# 23cm_amplifier.net
KiCad netlist of a schematic drawn in Altium Designer
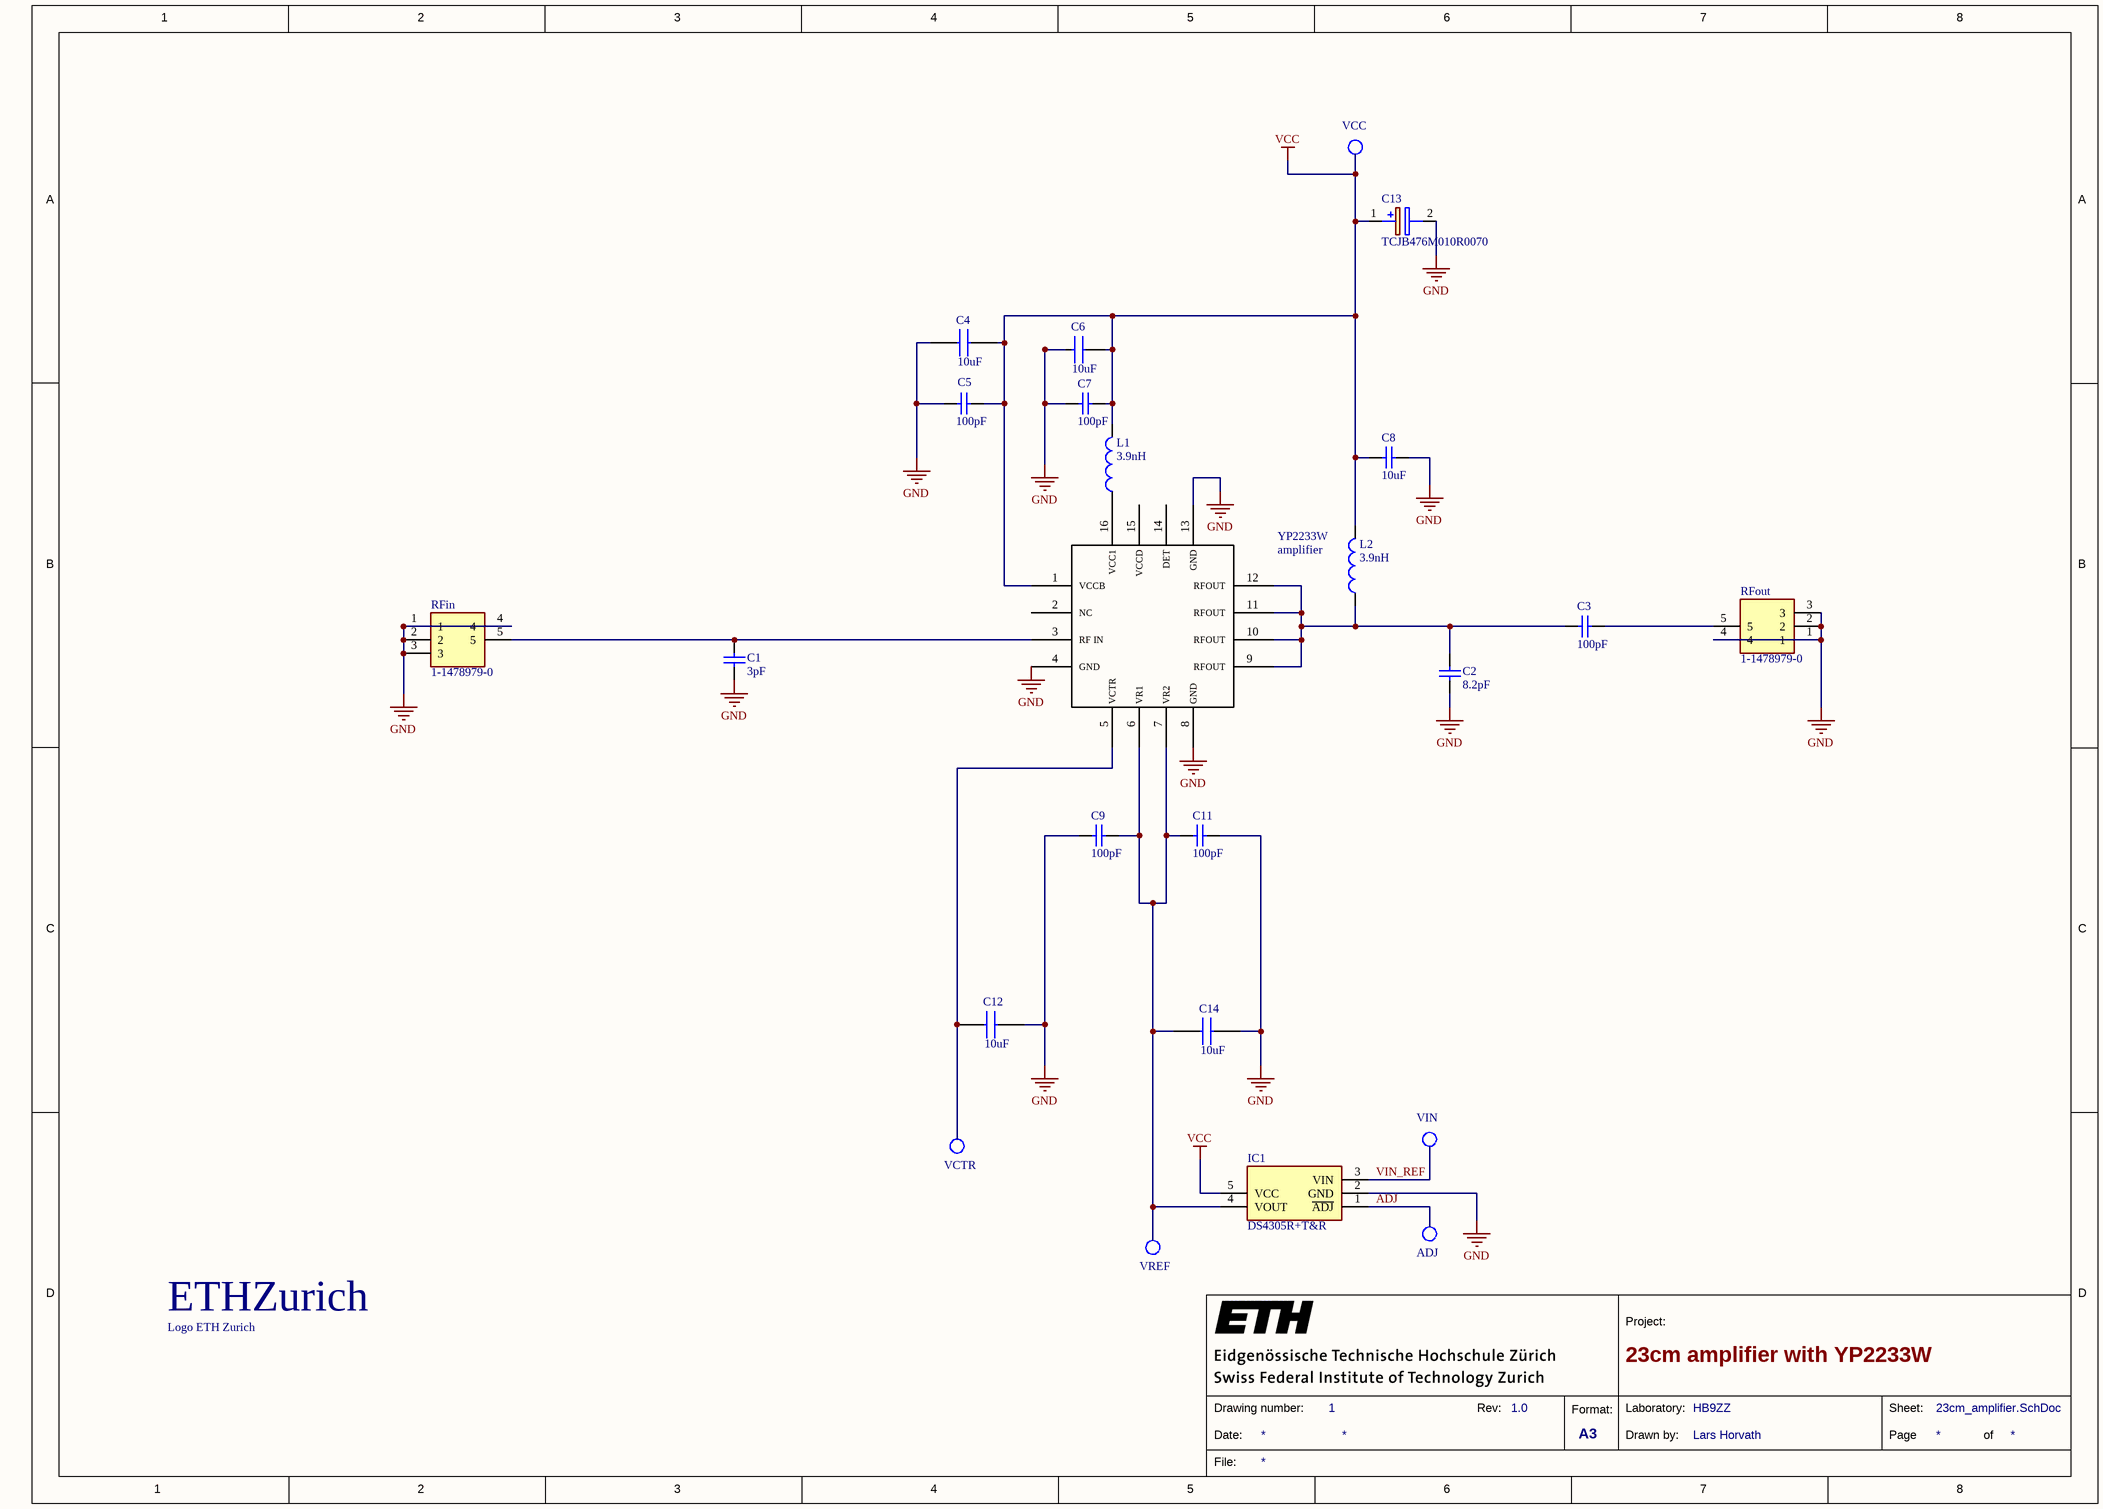
[diagram p0: 23cm_amplifier.SchDoc]

(export (version "E")
  (design (tool "Eeschema 10.0.6"))
  (components
    (comp (ref "A1")
      (value "Logo ETH Zurich")
      (footprint "eth-zurich_3mm")
      (libsource (lib "ETHZ Vault") (part "Logo ETH Zurich"))
    )
    (comp (ref "C1")
      (value "3pF")
      (footprint "CAPC0402(1005)70_N")
      (description "Silizium-HF-Kondensatoren / Dünnfilm 25V 3pF .05pFTol ThinFilm 0402")
      (fields (field (name "TOLERANCE") "5%") (field (name "MANUFACTURER") "Murata"))
      (libsource (lib "ETHZ Vault") (part "CAP"))
    )
    (comp (ref "C2")
      (value "8.2pF")
      (footprint "CAPC0402(1005)70_N")
      (description "Silizium-HF-Kondensatoren / Dünnfilm 16V 8.2pF .1pFTol ThinFilm 0402\r\nRoHS-konform")
      (fields (field (name "TOLERANCE") "5%") (field (name "MANUFACTURER") "Murata"))
      (libsource (lib "ETHZ Vault") (part "CAP"))
    )
    (comp (ref "C3")
      (value "100pF")
      (footprint "CAPC0402(1005)70_N")
      (fields
        (field (name "TOLERANCE") "5%")
        (field (name "MANUFACTURER") "TDK")
        (field (name "MANUFACTURER PART NUMBER") "C1005C0G1H101J050BE")
      )
      (libsource (lib "ETHZ Vault") (part "CAP"))
    )
    (comp (ref "C4")
      (value "C2012X8L1A106K125AC")
      (footprint "SamacSys:CAPC2012X145N")
      (description "Kondensator aus mehreren Keramikschichten MLCC - SMD/SMT 0805 10VDC 10uF 10% X8L")
      (fields (field (name "MOUSER PART NUMBER") "810-C2012X8L106K125C") (field (name "CAPACITY") "10uF"))
      (libsource (lib "*") (part "C2012X8L1A106K125AC"))
    )
    (comp (ref "C5")
      (value "100pF")
      (footprint "CAPC0402(1005)70_N")
      (fields
        (field (name "TOLERANCE") "5%")
        (field (name "MANUFACTURER") "TDK")
        (field (name "MANUFACTURER PART NUMBER") "C1005C0G1H101J050BE")
      )
      (libsource (lib "ETHZ Vault") (part "CAP"))
    )
    (comp (ref "C6")
      (value "C2012X8L1A106K125AC")
      (footprint "SamacSys:CAPC2012X145N")
      (description "Kondensator aus mehreren Keramikschichten MLCC - SMD/SMT 0805 10VDC 10uF 10% X8L")
      (fields (field (name "MOUSER PART NUMBER") "810-C2012X8L106K125C") (field (name "CAPACITY") "10uF"))
      (libsource (lib "*") (part "C2012X8L1A106K125AC"))
    )
    (comp (ref "C7")
      (value "100pF")
      (footprint "CAPC0402(1005)70_N")
      (fields
        (field (name "TOLERANCE") "5%")
        (field (name "MANUFACTURER") "TDK")
        (field (name "MANUFACTURER PART NUMBER") "C1005C0G1H101J050BE")
      )
      (libsource (lib "ETHZ Vault") (part "CAP"))
    )
    (comp (ref "C8")
      (value "10uF")
      (footprint "CAPC0402(1005)70_N")
      (description "Kondensator aus mehreren Keramikschichten MLCC - SMD/SMT 10UF 6.3V 20% 0402\r\nRoHS-konform")
      (fields (field (name "TOLERANCE") "5%") (field (name "MANUFACTURER") "Murata"))
      (libsource (lib "ETHZ Vault") (part "CAP"))
    )
    (comp (ref "C9")
      (value "100pF")
      (footprint "CAPC0402(1005)70_N")
      (fields
        (field (name "TOLERANCE") "5%")
        (field (name "MANUFACTURER") "TDK")
        (field (name "MANUFACTURER PART NUMBER") "C1005C0G1H101J050BE")
      )
      (libsource (lib "ETHZ Vault") (part "CAP"))
    )
    (comp (ref "C11")
      (value "100pF")
      (footprint "CAPC0402(1005)70_N")
      (fields
        (field (name "TOLERANCE") "5%")
        (field (name "MANUFACTURER") "TDK")
        (field (name "MANUFACTURER PART NUMBER") "C1005C0G1H101J050BE")
      )
      (libsource (lib "ETHZ Vault") (part "CAP"))
    )
    (comp (ref "C12")
      (value "C2012X8L1A106K125AC")
      (footprint "SamacSys:CAPC2012X145N")
      (description "Kondensator aus mehreren Keramikschichten MLCC - SMD/SMT 0805 10VDC 10uF 10% X8L")
      (fields (field (name "MOUSER PART NUMBER") "810-C2012X8L106K125C") (field (name "CAPACITY") "10uF"))
      (libsource (lib "*") (part "C2012X8L1A106K125AC"))
    )
    (comp (ref "C13")
      (value "TCJB476M010R0070")
      (footprint "SamacSys:CAPPM3528X210N")
      (description "Tantalum Capacitors - Polymer 10V 47uF 20% 1210 ESR=70mOhm")
      (fields (field (name "MOUSER PART NUMBER") "581-TCJB476M10R70"))
      (libsource (lib "*") (part "TCJB476M010R0070"))
    )
    (comp (ref "C14")
      (value "C2012X8L1A106K125AC")
      (footprint "SamacSys:CAPC2012X145N")
      (description "Kondensator aus mehreren Keramikschichten MLCC - SMD/SMT 0805 10VDC 10uF 10% X8L")
      (fields (field (name "MOUSER PART NUMBER") "810-C2012X8L106K125C") (field (name "CAPACITY") "10uF"))
      (libsource (lib "*") (part "C2012X8L1A106K125AC"))
    )
    (comp (ref "IC1")
      (value "DS4305R+T&R")
      (footprint "SamacSys:SOT95P280X145-5N")
      (description "Programmable Reference Voltage for 2.65V")
      (fields (field (name "MOUSER PART NUMBER") "700-DS4305RT&R"))
      (libsource (lib "*") (part "DS4305R+T&R"))
    )
    (comp (ref "L1")
      (value "3.9nH")
      (footprint "INDC1005X07N")
      (description "Festinduktivitäten 0402 3.9nH 1950mA 0.03ohms 10GHz")
      (fields (field (name "TOLERANCE") "5%") (field (name "Comment") "LQW15AN3N9B8ZD"))
      (libsource (lib "ETHZ Vault") (part "IND"))
    )
    (comp (ref "L2")
      (value "3.9nH")
      (footprint "INDC1005X07N")
      (description "Festinduktivitäten 0402 3.9nH 1950mA 0.03ohms 10GHz")
      (fields (field (name "TOLERANCE") "5%") (field (name "Comment") "LQW15AN3N9B8ZD"))
      (libsource (lib "ETHZ Vault") (part "IND"))
    )
    (comp (ref "RFin")
      (value "1-1478979-0")
      (footprint "SamacSys:114789790")
      (description "RF IN")
      (fields (field (name "MOUSER PART NUMBER") "571-1-1478979-0"))
      (libsource (lib "") (part "1-1478979-0_1"))
    )
    (comp (ref "RFout")
      (value "1-1478979-0")
      (footprint "SamacSys:114789790")
      (description "RF OUT")
      (fields (field (name "MOUSER PART NUMBER") "571-1-1478979-0"))
      (libsource (lib "*") (part "1-1478979-0"))
    )
    (comp (ref "YP2233W")
      (value "amplifier")
      (footprint "YP2233W")
      (libsource (lib "23cm_amplifier") (part "YP2233W"))
    )
  )
  (nets
    (net (code "1") (name "/ADJ") (class "Default")
      (node (ref "IC1") (pin "1") (pinfunction "~{ADJ}_1") (pintype "passive"))
    )
    (net (code "2") (name "/VIN_REF") (class "Default")
      (node (ref "IC1") (pin "3") (pinfunction "VIN_3") (pintype "passive"))
    )
    (net (code "3") (name "GND") (class "Default")
      (node (ref "C1") (pin "1") (pinfunction "1_1") (pintype "passive"))
      (node (ref "C11") (pin "2") (pinfunction "2_2") (pintype "passive"))
      (node (ref "C12") (pin "2") (pinfunction "2_2") (pintype "passive"))
      (node (ref "C13") (pin "2") (pinfunction "-_2") (pintype "passive"))
      (node (ref "C14") (pin "2") (pinfunction "2_2") (pintype "passive"))
      (node (ref "C2") (pin "1") (pinfunction "1_1") (pintype "passive"))
      (node (ref "C4") (pin "1") (pinfunction "1_1") (pintype "passive"))
      (node (ref "C5") (pin "1") (pinfunction "1_1") (pintype "passive"))
      (node (ref "C6") (pin "1") (pinfunction "1_1") (pintype "passive"))
      (node (ref "C7") (pin "1") (pinfunction "1_1") (pintype "passive"))
      (node (ref "C8") (pin "2") (pinfunction "2_2") (pintype "passive"))
      (node (ref "C9") (pin "1") (pinfunction "1_1") (pintype "passive"))
      (node (ref "IC1") (pin "2") (pinfunction "GND_2") (pintype "passive"))
      (node (ref "RFin") (pin "1") (pinfunction "1_1") (pintype "passive"))
      (node (ref "RFin") (pin "2") (pinfunction "2_2") (pintype "passive"))
      (node (ref "RFin") (pin "3") (pinfunction "3_3") (pintype "passive"))
      (node (ref "RFin") (pin "4") (pinfunction "4_4") (pintype "passive"))
      (node (ref "RFout") (pin "1") (pinfunction "1_1") (pintype "passive"))
      (node (ref "RFout") (pin "2") (pinfunction "2_2") (pintype "passive"))
      (node (ref "RFout") (pin "3") (pinfunction "3_3") (pintype "passive"))
      (node (ref "RFout") (pin "4") (pinfunction "4_4") (pintype "passive"))
      (node (ref "YP2233W") (pin "13") (pinfunction "GND_13") (pintype "passive"))
      (node (ref "YP2233W") (pin "4") (pinfunction "GND_4") (pintype "passive"))
      (node (ref "YP2233W") (pin "8") (pinfunction "GND_8") (pintype "passive"))
    )
    (net (code "4") (name "Net-(C2-Pad2)") (class "Default")
      (node (ref "C2") (pin "2") (pinfunction "2_2") (pintype "passive"))
      (node (ref "C3") (pin "1") (pinfunction "1_1") (pintype "passive"))
      (node (ref "L2") (pin "1") (pinfunction "1_1") (pintype "passive"))
      (node (ref "YP2233W") (pin "10") (pinfunction "RFOUT_10") (pintype "passive"))
      (node (ref "YP2233W") (pin "11") (pinfunction "RFOUT_11") (pintype "passive"))
      (node (ref "YP2233W") (pin "12") (pinfunction "RFOUT_12") (pintype "passive"))
      (node (ref "YP2233W") (pin "9") (pinfunction "RFOUT_9") (pintype "passive"))
    )
    (net (code "5") (name "Net-(C3-Pad2)") (class "Default")
      (node (ref "C3") (pin "2") (pinfunction "2_2") (pintype "passive"))
      (node (ref "RFout") (pin "5") (pinfunction "5_5") (pintype "passive"))
    )
    (net (code "6") (name "Net-(IC1-VOUT)") (class "Default")
      (node (ref "C11") (pin "1") (pinfunction "1_1") (pintype "passive"))
      (node (ref "C14") (pin "1") (pinfunction "1_1") (pintype "passive"))
      (node (ref "C9") (pin "2") (pinfunction "2_2") (pintype "passive"))
      (node (ref "IC1") (pin "4") (pinfunction "VOUT_4") (pintype "passive"))
      (node (ref "YP2233W") (pin "6") (pinfunction "VR1_6") (pintype "passive"))
      (node (ref "YP2233W") (pin "7") (pinfunction "VR2_7") (pintype "passive"))
    )
    (net (code "7") (name "Net-(YP2233W-RF_IN)") (class "Default")
      (node (ref "C1") (pin "2") (pinfunction "2_2") (pintype "passive"))
      (node (ref "RFin") (pin "5") (pinfunction "5_5") (pintype "passive"))
      (node (ref "YP2233W") (pin "3") (pinfunction "RF_IN_3") (pintype "passive"))
    )
    (net (code "8") (name "Net-(YP2233W-VCC1)") (class "Default")
      (node (ref "L1") (pin "1") (pinfunction "1_1") (pintype "passive"))
      (node (ref "YP2233W") (pin "16") (pinfunction "VCC1_16") (pintype "passive"))
    )
    (net (code "9") (name "Net-(YP2233W-VCTR)") (class "Default")
      (node (ref "C12") (pin "1") (pinfunction "1_1") (pintype "passive"))
      (node (ref "YP2233W") (pin "5") (pinfunction "VCTR_5") (pintype "passive"))
    )
    (net (code "10") (name "VCC") (class "Default")
      (node (ref "C13") (pin "1") (pinfunction "+_1") (pintype "passive"))
      (node (ref "C4") (pin "2") (pinfunction "2_2") (pintype "passive"))
      (node (ref "C5") (pin "2") (pinfunction "2_2") (pintype "passive"))
      (node (ref "C6") (pin "2") (pinfunction "2_2") (pintype "passive"))
      (node (ref "C7") (pin "2") (pinfunction "2_2") (pintype "passive"))
      (node (ref "C8") (pin "1") (pinfunction "1_1") (pintype "passive"))
      (node (ref "IC1") (pin "5") (pinfunction "VCC_5") (pintype "passive"))
      (node (ref "L1") (pin "2") (pinfunction "2_2") (pintype "passive"))
      (node (ref "L2") (pin "2") (pinfunction "2_2") (pintype "passive"))
      (node (ref "YP2233W") (pin "1") (pinfunction "VCCB_1") (pintype "passive"))
    )
    (net (code "11") (name "unconnected-(YP2233W-DET-Pad14)") (class "Default")
      (node (ref "YP2233W") (pin "14") (pinfunction "DET_14") (pintype "passive"))
    )
    (net (code "12") (name "unconnected-(YP2233W-NC-Pad2)") (class "Default")
      (node (ref "YP2233W") (pin "2") (pinfunction "NC_2") (pintype "passive"))
    )
    (net (code "13") (name "unconnected-(YP2233W-VCCD-Pad15)") (class "Default")
      (node (ref "YP2233W") (pin "15") (pinfunction "VCCD_15") (pintype "passive"))
    )
  )
)
